# Type4me.net
KiCad netlist of a schematic drawn in EAGLE
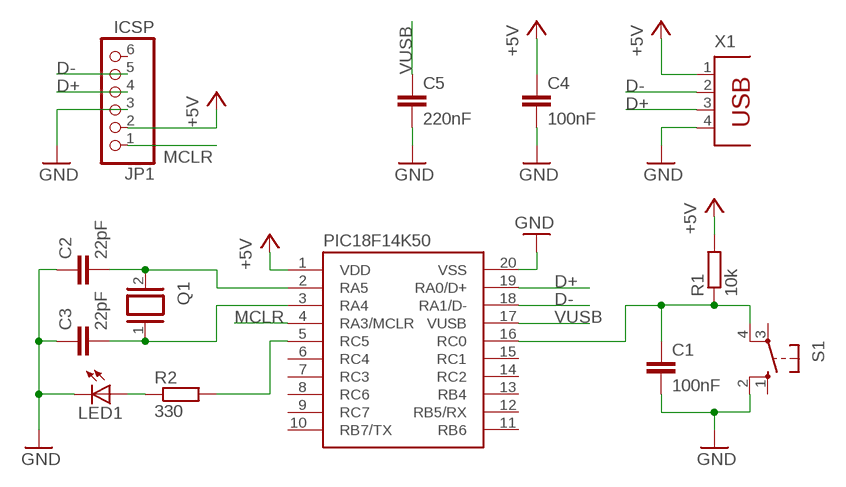
[diagram p0: schematic, sheet 1]

(export (version "E")
  (design (tool "Eeschema 10.0.6"))
  (components
    (comp (ref "C1")
      (value "100nF")
      (footprint "eagle-import:C050-030X075")
      (libsource (lib "eagle-import") (part "C-EU050-030X075"))
    )
    (comp (ref "C2")
      (value "22pF")
      (footprint "eagle-import:C025-030X050")
      (libsource (lib "eagle-import") (part "C-EU025-030X050"))
    )
    (comp (ref "C3")
      (value "22pF")
      (footprint "eagle-import:C025-030X050")
      (libsource (lib "eagle-import") (part "C-EU025-030X050"))
    )
    (comp (ref "C4")
      (value "100nF")
      (footprint "eagle-import:C050-030X075")
      (libsource (lib "eagle-import") (part "C-EU050-030X075"))
    )
    (comp (ref "C5")
      (value "220nF")
      (footprint "eagle-import:C050-030X075")
      (libsource (lib "eagle-import") (part "C-EU050-030X075"))
    )
    (comp (ref "JP1")
      (value "ICSP")
      (footprint "eagle-import:1X06")
      (libsource (lib "eagle-import") (part "PINHD-1X6"))
    )
    (comp (ref "LED1")
      (value "LED5MM")
      (footprint "eagle-import:LED5MM")
      (libsource (lib "eagle-import") (part "LED5MM"))
    )
    (comp (ref "Q1")
      (value "XTAL/S")
      (footprint "eagle-import:QS")
      (libsource (lib "eagle-import") (part "XTAL/S"))
    )
    (comp (ref "R1")
      (value "10k")
      (footprint "eagle-import:0207_12")
      (libsource (lib "eagle-import") (part "R-EU_0207/12"))
    )
    (comp (ref "R2")
      (value "330")
      (footprint "eagle-import:0207_12")
      (libsource (lib "eagle-import") (part "R-EU_0207/12"))
    )
    (comp (ref "S1")
      (value "10-XX")
      (footprint "eagle-import:B3F-10XX")
      (fields (field (name "MPN") "B3F-1000"))
      (libsource (lib "eagle-import") (part "10-XX"))
    )
    (comp (ref "U$1")
      (value "PIC18F14K50")
      (footprint "eagle-import:DIP-20")
      (libsource (lib "eagle-import") (part "PIC18F14K50"))
    )
    (comp (ref "X1")
      (value "PN61729")
      (footprint "eagle-import:PN61729")
      (libsource (lib "eagle-import") (part "PN61729"))
    )
  )
  (nets
    (net (code "1") (name "+5V") (class "Default")
      (node (ref "C4") (pin "1") (pinfunction "1_1") (pintype "passive"))
      (node (ref "JP1") (pin "2") (pinfunction "2_2") (pintype "passive"))
      (node (ref "R1") (pin "2") (pinfunction "2_2") (pintype "passive"))
      (node (ref "U$1") (pin "1") (pinfunction "VDD_1") (pintype "bidirectional"))
      (node (ref "X1") (pin "1") (pinfunction "1_1") (pintype "passive"))
    )
    (net (code "2") (name "/D+") (class "Default")
      (node (ref "JP1") (pin "4") (pinfunction "4_4") (pintype "passive"))
      (node (ref "U$1") (pin "19") (pinfunction "RA0/D+_19") (pintype "bidirectional"))
      (node (ref "X1") (pin "3") (pinfunction "3_3") (pintype "passive"))
    )
    (net (code "3") (name "/D-") (class "Default")
      (node (ref "JP1") (pin "5") (pinfunction "5_5") (pintype "passive"))
      (node (ref "U$1") (pin "18") (pinfunction "RA1/D-_18") (pintype "bidirectional"))
      (node (ref "X1") (pin "2") (pinfunction "2_2") (pintype "passive"))
    )
    (net (code "4") (name "/MCLR") (class "Default")
      (node (ref "JP1") (pin "1") (pinfunction "1_1") (pintype "passive"))
      (node (ref "U$1") (pin "4") (pinfunction "RA3/MCLR_4") (pintype "bidirectional"))
    )
    (net (code "5") (name "/VUSB") (class "Default")
      (node (ref "C5") (pin "1") (pinfunction "1_1") (pintype "passive"))
      (node (ref "U$1") (pin "17") (pinfunction "VUSB_17") (pintype "bidirectional"))
    )
    (net (code "6") (name "GND") (class "Default")
      (node (ref "C1") (pin "2") (pinfunction "2_2") (pintype "passive"))
      (node (ref "C2") (pin "1") (pinfunction "1_1") (pintype "passive"))
      (node (ref "C3") (pin "1") (pinfunction "1_1") (pintype "passive"))
      (node (ref "C4") (pin "2") (pinfunction "2_2") (pintype "passive"))
      (node (ref "C5") (pin "2") (pinfunction "2_2") (pintype "passive"))
      (node (ref "JP1") (pin "3") (pinfunction "3_3") (pintype "passive"))
      (node (ref "LED1") (pin "K") (pinfunction "C_K") (pintype "passive"))
      (node (ref "S1") (pin "2") (pinfunction "S1_2") (pintype "passive"))
      (node (ref "U$1") (pin "20") (pinfunction "VSS_20") (pintype "bidirectional"))
      (node (ref "X1") (pin "4") (pinfunction "4_4") (pintype "passive"))
    )
    (net (code "7") (name "Net-(LED1-PadA)") (class "Default")
      (node (ref "LED1") (pin "A") (pinfunction "A_A") (pintype "passive"))
      (node (ref "R2") (pin "1") (pinfunction "1_1") (pintype "passive"))
    )
    (net (code "8") (name "Net-(S1-P1)") (class "Default")
      (node (ref "C1") (pin "1") (pinfunction "1_1") (pintype "passive"))
      (node (ref "R1") (pin "1") (pinfunction "1_1") (pintype "passive"))
      (node (ref "S1") (pin "4") (pinfunction "P1_4") (pintype "passive"))
      (node (ref "U$1") (pin "16") (pinfunction "RC0_16") (pintype "bidirectional"))
    )
    (net (code "9") (name "Net-(U$1-RA4)") (class "Default")
      (node (ref "C3") (pin "2") (pinfunction "2_2") (pintype "passive"))
      (node (ref "Q1") (pin "1") (pinfunction "1_1") (pintype "passive"))
      (node (ref "U$1") (pin "3") (pinfunction "RA4_3") (pintype "bidirectional"))
    )
    (net (code "10") (name "Net-(U$1-RA5)") (class "Default")
      (node (ref "C2") (pin "2") (pinfunction "2_2") (pintype "passive"))
      (node (ref "Q1") (pin "2") (pinfunction "2_2") (pintype "passive"))
      (node (ref "U$1") (pin "2") (pinfunction "RA5_2") (pintype "bidirectional"))
    )
    (net (code "11") (name "Net-(U$1-RC5)") (class "Default")
      (node (ref "R2") (pin "2") (pinfunction "2_2") (pintype "passive"))
      (node (ref "U$1") (pin "5") (pinfunction "RC5_5") (pintype "bidirectional"))
    )
    (net (code "12") (name "unconnected-(JP1-Pad6)") (class "Default")
      (node (ref "JP1") (pin "6") (pinfunction "6_6") (pintype "passive"))
    )
    (net (code "13") (name "unconnected-(S1-P-Pad3)") (class "Default")
      (node (ref "S1") (pin "3") (pinfunction "P_3") (pintype "passive"))
    )
    (net (code "14") (name "unconnected-(S1-S-Pad1)") (class "Default")
      (node (ref "S1") (pin "1") (pinfunction "S_1") (pintype "passive"))
    )
    (net (code "15") (name "unconnected-(U$1-RB4-Pad13)") (class "Default")
      (node (ref "U$1") (pin "13") (pinfunction "RB4_13") (pintype "bidirectional"))
    )
    (net (code "16") (name "unconnected-(U$1-RB5{slash}RX-Pad12)") (class "Default")
      (node (ref "U$1") (pin "12") (pinfunction "RB5/RX_12") (pintype "bidirectional"))
    )
    (net (code "17") (name "unconnected-(U$1-RB6-Pad11)") (class "Default")
      (node (ref "U$1") (pin "11") (pinfunction "RB6_11") (pintype "bidirectional"))
    )
    (net (code "18") (name "unconnected-(U$1-RB7{slash}TX-Pad10)") (class "Default")
      (node (ref "U$1") (pin "10") (pinfunction "RB7/TX_10") (pintype "bidirectional"))
    )
    (net (code "19") (name "unconnected-(U$1-RC1-Pad15)") (class "Default")
      (node (ref "U$1") (pin "15") (pinfunction "RC1_15") (pintype "bidirectional"))
    )
    (net (code "20") (name "unconnected-(U$1-RC2-Pad14)") (class "Default")
      (node (ref "U$1") (pin "14") (pinfunction "RC2_14") (pintype "bidirectional"))
    )
    (net (code "21") (name "unconnected-(U$1-RC3-Pad7)") (class "Default")
      (node (ref "U$1") (pin "7") (pinfunction "RC3_7") (pintype "bidirectional"))
    )
    (net (code "22") (name "unconnected-(U$1-RC4-Pad6)") (class "Default")
      (node (ref "U$1") (pin "6") (pinfunction "RC4_6") (pintype "bidirectional"))
    )
    (net (code "23") (name "unconnected-(U$1-RC6-Pad8)") (class "Default")
      (node (ref "U$1") (pin "8") (pinfunction "RC6_8") (pintype "bidirectional"))
    )
    (net (code "24") (name "unconnected-(U$1-RC7-Pad9)") (class "Default")
      (node (ref "U$1") (pin "9") (pinfunction "RC7_9") (pintype "bidirectional"))
    )
  )
)
